# PiPSU.net
KiCad netlist of a schematic drawn in EAGLE
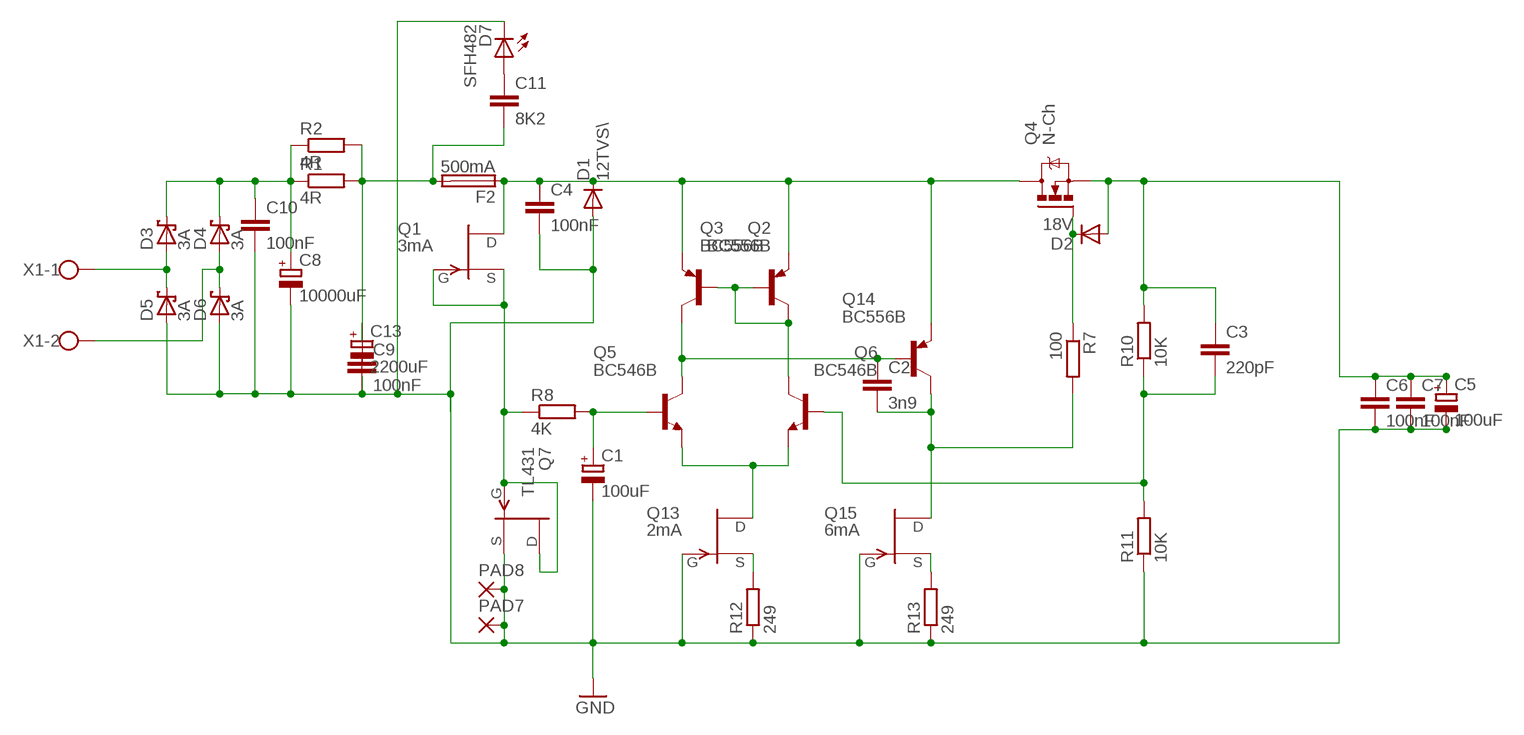
[diagram p0: schematic, sheet 1]

(export (version "E")
  (design (tool "Eeschema 10.0.6"))
  (components
    (comp (ref "C1")
      (value "100uF")
      (footprint "eagle-import:E3,5-8")
      (libsource (lib "eagle-import") (part "CPOL-EUE3.5-8"))
    )
    (comp (ref "C2")
      (value "3n9")
      (footprint "eagle-import:C1210K")
      (libsource (lib "eagle-import") (part "C-EUC1210K"))
    )
    (comp (ref "C3")
      (value "220pF")
      (footprint "eagle-import:C1210")
      (libsource (lib "eagle-import") (part "C-EUC1210"))
    )
    (comp (ref "C4")
      (value "100nF")
      (footprint "eagle-import:C1210")
      (libsource (lib "eagle-import") (part "C-EUC1210"))
    )
    (comp (ref "C5")
      (value "100uF")
      (footprint "eagle-import:E3,5-8")
      (libsource (lib "eagle-import") (part "CPOL-EUE3.5-8"))
    )
    (comp (ref "C6")
      (value "100nF")
      (footprint "eagle-import:C1210")
      (libsource (lib "eagle-import") (part "C-EUC1210"))
    )
    (comp (ref "C7")
      (value "100nF")
      (footprint "eagle-import:C1210")
      (libsource (lib "eagle-import") (part "C-EUC1210"))
    )
    (comp (ref "C8")
      (value "10000uF")
      (footprint "eagle-import:E7,5-18")
      (libsource (lib "eagle-import") (part "CPOL-EUE7.5-18"))
    )
    (comp (ref "C9")
      (value "100nF")
      (footprint "eagle-import:C102-043X133")
      (libsource (lib "eagle-import") (part "C-EU102-043X133"))
    )
    (comp (ref "C10")
      (value "100nF")
      (footprint "eagle-import:C1210")
      (libsource (lib "eagle-import") (part "C-EUC1210"))
    )
    (comp (ref "C11")
      (value "8K2")
      (footprint "eagle-import:C1210")
      (libsource (lib "eagle-import") (part "C-EUC1210"))
    )
    (comp (ref "C13")
      (value "2200uF")
      (footprint "eagle-import:E7,5-18")
      (libsource (lib "eagle-import") (part "CPOL-EUE7.5-18"))
    )
    (comp (ref "D1")
      (value "12TVS\\")
      (footprint "eagle-import:DO35-10")
      (libsource (lib "eagle-import") (part "1N4148DO35-10"))
    )
    (comp (ref "D2")
      (value "18V")
      (footprint "eagle-import:DO35-7")
      (libsource (lib "eagle-import") (part "1N4148DO35-7"))
    )
    (comp (ref "D3")
      (value "3A")
      (footprint "eagle-import:SMC")
      (libsource (lib "eagle-import") (part "MBRS30T33"))
    )
    (comp (ref "D4")
      (value "3A")
      (footprint "eagle-import:SMC")
      (libsource (lib "eagle-import") (part "MBRS30T33"))
    )
    (comp (ref "D5")
      (value "3A")
      (footprint "eagle-import:SMC")
      (libsource (lib "eagle-import") (part "MBRS30T33"))
    )
    (comp (ref "D6")
      (value "3A")
      (footprint "eagle-import:SMC")
      (libsource (lib "eagle-import") (part "MBRS30T33"))
    )
    (comp (ref "D7")
      (value "SFH482")
      (footprint "eagle-import:SFH482")
      (libsource (lib "eagle-import") (part "SFH482"))
    )
    (comp (ref "F2")
      (value "500mA")
      (footprint "eagle-import:19560")
      (libsource (lib "eagle-import") (part "19560"))
    )
    (comp (ref "PAD7")
      (value "3,81/1,4")
      (footprint "eagle-import:3,81_1,4")
      (libsource (lib "eagle-import") (part "3,81/1,4"))
    )
    (comp (ref "PAD8")
      (value "3,81/1,4")
      (footprint "eagle-import:3,81_1,4")
      (libsource (lib "eagle-import") (part "3,81/1,4"))
    )
    (comp (ref "Q1")
      (value "3mA")
      (footprint "eagle-import:TO92-")
      (libsource (lib "eagle-import") (part "?5482N4"))
    )
    (comp (ref "Q2")
      (value "BC556B")
      (footprint "eagle-import:TO92-EBC")
      (libsource (lib "eagle-import") (part "BC560"))
    )
    (comp (ref "Q3")
      (value "BC556B")
      (footprint "eagle-import:TO92-EBC")
      (libsource (lib "eagle-import") (part "BC560"))
    )
    (comp (ref "Q4")
      (value "N-Ch")
      (footprint "eagle-import:TO-247AD-H")
      (libsource (lib "eagle-import") (part "IXF?6NH_90"))
    )
    (comp (ref "Q5")
      (value "BC546B")
      (footprint "eagle-import:TO92-EBC")
      (libsource (lib "eagle-import") (part "BC550B"))
    )
    (comp (ref "Q6")
      (value "BC546B")
      (footprint "eagle-import:TO92-EBC")
      (libsource (lib "eagle-import") (part "BC550B"))
    )
    (comp (ref "Q7")
      (value "TL431")
      (footprint "eagle-import:TO92-")
      (libsource (lib "eagle-import") (part "?5482N4"))
    )
    (comp (ref "Q13")
      (value "2mA")
      (footprint "eagle-import:TO92-")
      (libsource (lib "eagle-import") (part "?5482N4"))
    )
    (comp (ref "Q14")
      (value "BC556B")
      (footprint "eagle-import:TO92-EBC")
      (libsource (lib "eagle-import") (part "BC560"))
    )
    (comp (ref "Q15")
      (value "6mA")
      (footprint "eagle-import:TO92-")
      (libsource (lib "eagle-import") (part "?5482N4"))
    )
    (comp (ref "R1")
      (value "4R")
      (footprint "eagle-import:0309_12")
      (libsource (lib "eagle-import") (part "R-EU_0309/12"))
    )
    (comp (ref "R2")
      (value "4R")
      (footprint "eagle-import:0309_12")
      (libsource (lib "eagle-import") (part "R-EU_0309/12"))
    )
    (comp (ref "R7")
      (value "100")
      (footprint "eagle-import:0309_12")
      (libsource (lib "eagle-import") (part "R-EU_0309/12"))
    )
    (comp (ref "R8")
      (value "4K")
      (footprint "eagle-import:0309_12")
      (libsource (lib "eagle-import") (part "R-EU_0309/12"))
    )
    (comp (ref "R10")
      (value "10K")
      (footprint "eagle-import:R1210")
      (libsource (lib "eagle-import") (part "R-EU_R1210"))
    )
    (comp (ref "R11")
      (value "10K")
      (footprint "eagle-import:R1210")
      (libsource (lib "eagle-import") (part "R-EU_R1210"))
    )
    (comp (ref "R12")
      (value "249")
      (footprint "eagle-import:R1210")
      (libsource (lib "eagle-import") (part "R-EU_R1210"))
    )
    (comp (ref "R13")
      (value "249")
      (footprint "eagle-import:R1210")
      (libsource (lib "eagle-import") (part "R-EU_R1210"))
    )
    (comp (ref "X1")
      (value "W237-102")
      (footprint "eagle-import:W237-102")
      (fields
        (field (name "MPN") "237-102")
        (field (name "MPN_1") "237-102")
        (field (name "OC_FARNELL") "unknown")
        (field (name "OC_NEWARK") "70K9898")
      )
      (libsource (lib "eagle-import") (part "W237-102"))
    )
  )
  (nets
    (net (code "1") (name "GND") (class "Default")
      (node (ref "C1") (pin "-") (pinfunction "-_-") (pintype "passive"))
      (node (ref "C10") (pin "2") (pinfunction "2_2") (pintype "passive"))
      (node (ref "C13") (pin "-") (pinfunction "-_-") (pintype "passive"))
      (node (ref "C4") (pin "2") (pinfunction "2_2") (pintype "passive"))
      (node (ref "C5") (pin "-") (pinfunction "-_-") (pintype "passive"))
      (node (ref "C6") (pin "2") (pinfunction "2_2") (pintype "passive"))
      (node (ref "C7") (pin "2") (pinfunction "2_2") (pintype "passive"))
      (node (ref "C8") (pin "-") (pinfunction "-_-") (pintype "passive"))
      (node (ref "C9") (pin "2") (pinfunction "2_2") (pintype "passive"))
      (node (ref "D1") (pin "A") (pinfunction "A_A") (pintype "passive"))
      (node (ref "D5") (pin "A") (pinfunction "A_A") (pintype "passive"))
      (node (ref "D6") (pin "A") (pinfunction "A_A") (pintype "passive"))
      (node (ref "D7") (pin "K") (pinfunction "C_K") (pintype "passive"))
      (node (ref "PAD7") (pin "1") (pinfunction "P_1") (pintype "passive"))
      (node (ref "PAD8") (pin "1") (pinfunction "P_1") (pintype "passive"))
      (node (ref "Q13") (pin "1") (pinfunction "G_1") (pintype "passive"))
      (node (ref "Q15") (pin "1") (pinfunction "G_1") (pintype "passive"))
      (node (ref "Q7") (pin "2") (pinfunction "S_2") (pintype "passive"))
      (node (ref "R11") (pin "1") (pinfunction "1_1") (pintype "passive"))
      (node (ref "R12") (pin "1") (pinfunction "1_1") (pintype "passive"))
      (node (ref "R13") (pin "1") (pinfunction "1_1") (pintype "passive"))
    )
    (net (code "2") (name "Net-(C1-Pad+)") (class "Default")
      (node (ref "C1") (pin "+") (pinfunction "+_+") (pintype "passive"))
      (node (ref "Q5") (pin "B") (pinfunction "B_B") (pintype "passive"))
      (node (ref "R8") (pin "2") (pinfunction "2_2") (pintype "passive"))
    )
    (net (code "3") (name "Net-(C2-Pad1)") (class "Default")
      (node (ref "C2") (pin "1") (pinfunction "1_1") (pintype "passive"))
      (node (ref "Q14") (pin "B") (pinfunction "B_B") (pintype "passive"))
      (node (ref "Q2") (pin "C") (pinfunction "C_C") (pintype "passive"))
      (node (ref "Q5") (pin "C") (pinfunction "C_C") (pintype "passive"))
    )
    (net (code "4") (name "Net-(C3-Pad1)") (class "Default")
      (node (ref "C3") (pin "1") (pinfunction "1_1") (pintype "passive"))
      (node (ref "C5") (pin "+") (pinfunction "+_+") (pintype "passive"))
      (node (ref "C6") (pin "1") (pinfunction "1_1") (pintype "passive"))
      (node (ref "C7") (pin "1") (pinfunction "1_1") (pintype "passive"))
      (node (ref "D2") (pin "A") (pinfunction "A_A") (pintype "passive"))
      (node (ref "Q4") (pin "S") (pinfunction "S_S") (pintype "passive"))
      (node (ref "R10") (pin "2") (pinfunction "2_2") (pintype "passive"))
    )
    (net (code "5") (name "Net-(C3-Pad2)") (class "Default")
      (node (ref "C3") (pin "2") (pinfunction "2_2") (pintype "passive"))
      (node (ref "Q6") (pin "B") (pinfunction "B_B") (pintype "passive"))
      (node (ref "R10") (pin "1") (pinfunction "1_1") (pintype "passive"))
      (node (ref "R11") (pin "2") (pinfunction "2_2") (pintype "passive"))
    )
    (net (code "6") (name "Net-(C10-Pad1)") (class "Default")
      (node (ref "C10") (pin "1") (pinfunction "1_1") (pintype "passive"))
      (node (ref "C8") (pin "+") (pinfunction "+_+") (pintype "passive"))
      (node (ref "D3") (pin "C") (pinfunction "C_C") (pintype "passive"))
      (node (ref "D4") (pin "C") (pinfunction "C_C") (pintype "passive"))
      (node (ref "R1") (pin "1") (pinfunction "1_1") (pintype "passive"))
      (node (ref "R2") (pin "1") (pinfunction "1_1") (pintype "passive"))
    )
    (net (code "7") (name "Net-(C11-Pad1)") (class "Default")
      (node (ref "C11") (pin "1") (pinfunction "1_1") (pintype "passive"))
      (node (ref "D7") (pin "A") (pinfunction "A_A") (pintype "passive"))
    )
    (net (code "8") (name "Net-(C11-Pad2)") (class "Default")
      (node (ref "C11") (pin "2") (pinfunction "2_2") (pintype "passive"))
      (node (ref "C13") (pin "+") (pinfunction "+_+") (pintype "passive"))
      (node (ref "C9") (pin "1") (pinfunction "1_1") (pintype "passive"))
      (node (ref "F2") (pin "2") (pinfunction "2_2") (pintype "passive"))
      (node (ref "R1") (pin "2") (pinfunction "2_2") (pintype "passive"))
      (node (ref "R2") (pin "2") (pinfunction "2_2") (pintype "passive"))
    )
    (net (code "9") (name "Net-(D2-PadC)") (class "Default")
      (node (ref "D2") (pin "C") (pinfunction "C_C") (pintype "passive"))
      (node (ref "Q4") (pin "G") (pinfunction "G_G") (pintype "passive"))
      (node (ref "R7") (pin "1") (pinfunction "1_1") (pintype "passive"))
    )
    (net (code "10") (name "Net-(Q1-D)") (class "Default")
      (node (ref "C4") (pin "1") (pinfunction "1_1") (pintype "passive"))
      (node (ref "D1") (pin "C") (pinfunction "C_C") (pintype "passive"))
      (node (ref "F2") (pin "1") (pinfunction "1_1") (pintype "passive"))
      (node (ref "Q1") (pin "3") (pinfunction "D_3") (pintype "passive"))
      (node (ref "Q14") (pin "E") (pinfunction "E_E") (pintype "passive"))
      (node (ref "Q2") (pin "E") (pinfunction "E_E") (pintype "passive"))
      (node (ref "Q3") (pin "E") (pinfunction "E_E") (pintype "passive"))
      (node (ref "Q4") (pin "D") (pinfunction "D_D") (pintype "passive"))
    )
    (net (code "11") (name "Net-(Q1-G)") (class "Default")
      (node (ref "Q1") (pin "1") (pinfunction "G_1") (pintype "passive"))
      (node (ref "Q1") (pin "2") (pinfunction "S_2") (pintype "passive"))
      (node (ref "Q7") (pin "1") (pinfunction "G_1") (pintype "passive"))
      (node (ref "Q7") (pin "3") (pinfunction "D_3") (pintype "passive"))
      (node (ref "R8") (pin "1") (pinfunction "1_1") (pintype "passive"))
    )
    (net (code "12") (name "Net-(Q2-PadB)") (class "Default")
      (node (ref "Q2") (pin "B") (pinfunction "B_B") (pintype "passive"))
      (node (ref "Q3") (pin "B") (pinfunction "B_B") (pintype "passive"))
      (node (ref "Q3") (pin "C") (pinfunction "C_C") (pintype "passive"))
      (node (ref "Q6") (pin "C") (pinfunction "C_C") (pintype "passive"))
    )
    (net (code "13") (name "Net-(Q13-D)") (class "Default")
      (node (ref "Q13") (pin "3") (pinfunction "D_3") (pintype "passive"))
      (node (ref "Q5") (pin "E") (pinfunction "E_E") (pintype "passive"))
      (node (ref "Q6") (pin "E") (pinfunction "E_E") (pintype "passive"))
    )
    (net (code "14") (name "Net-(Q13-S)") (class "Default")
      (node (ref "Q13") (pin "2") (pinfunction "S_2") (pintype "passive"))
      (node (ref "R12") (pin "2") (pinfunction "2_2") (pintype "passive"))
    )
    (net (code "15") (name "Net-(Q15-D)") (class "Default")
      (node (ref "C2") (pin "2") (pinfunction "2_2") (pintype "passive"))
      (node (ref "Q14") (pin "C") (pinfunction "C_C") (pintype "passive"))
      (node (ref "Q15") (pin "3") (pinfunction "D_3") (pintype "passive"))
      (node (ref "R7") (pin "2") (pinfunction "2_2") (pintype "passive"))
    )
    (net (code "16") (name "Net-(Q15-S)") (class "Default")
      (node (ref "Q15") (pin "2") (pinfunction "S_2") (pintype "passive"))
      (node (ref "R13") (pin "2") (pinfunction "2_2") (pintype "passive"))
    )
    (net (code "17") (name "Net-(X1A-KL)") (class "Default")
      (node (ref "D3") (pin "A") (pinfunction "A_A") (pintype "passive"))
      (node (ref "D5") (pin "C") (pinfunction "C_C") (pintype "passive"))
      (node (ref "X1") (pin "1") (pinfunction "KL_1") (pintype "passive"))
    )
    (net (code "18") (name "Net-(X1B-KL)") (class "Default")
      (node (ref "D4") (pin "A") (pinfunction "A_A") (pintype "passive"))
      (node (ref "D6") (pin "C") (pinfunction "C_C") (pintype "passive"))
      (node (ref "X1") (pin "2") (pinfunction "KL_2") (pintype "passive"))
    )
  )
)
